# RH046_2.net
KiCad netlist of a schematic drawn in EAGLE
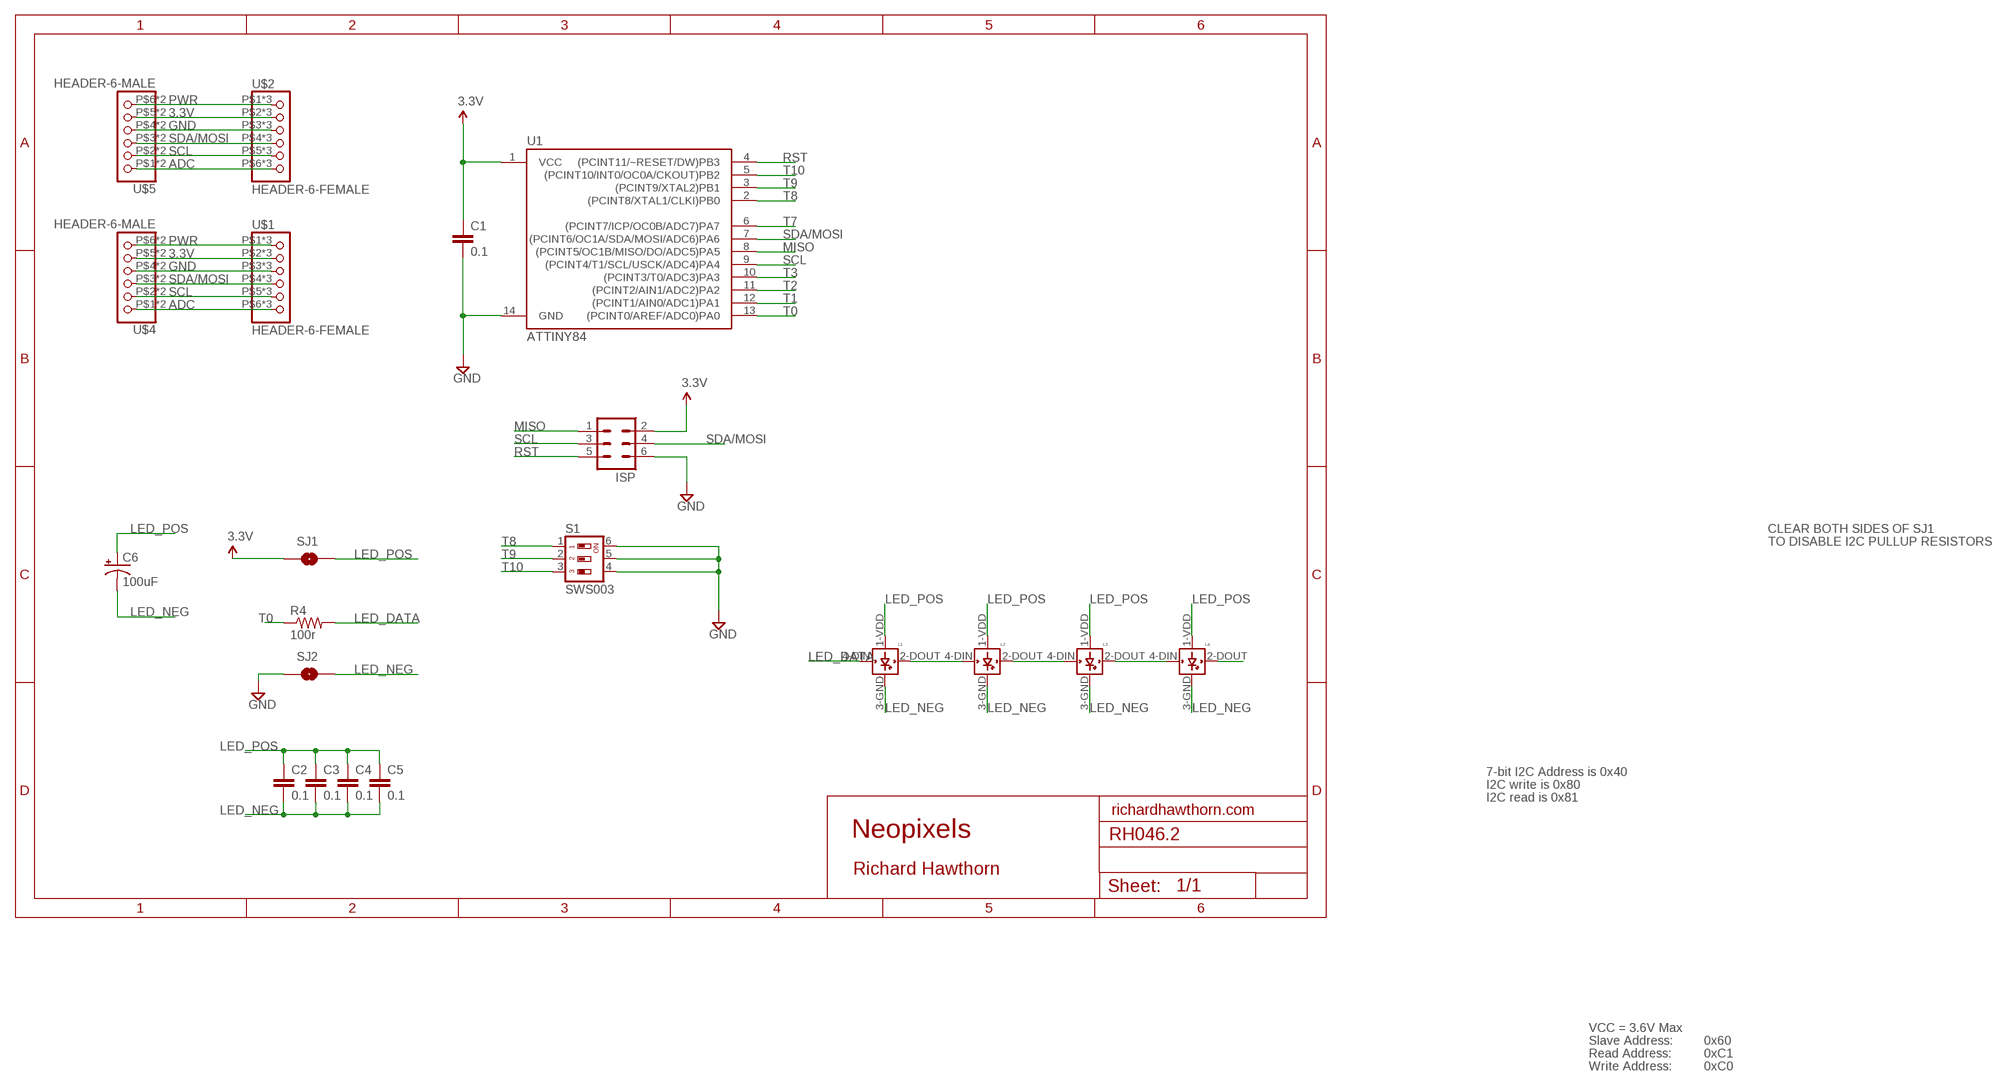
[diagram p0: schematic, sheet 1]

(export (version "E")
  (design (tool "Eeschema 10.0.6"))
  (components
    (comp (ref "C1")
      (value "0.1")
      (footprint "eagle-import:0603-CAP")
      (libsource (lib "eagle-import") (part "CAP0603-CAP"))
    )
    (comp (ref "C2")
      (value "0.1")
      (footprint "eagle-import:0603-CAP")
      (libsource (lib "eagle-import") (part "CAP0603-CAP"))
    )
    (comp (ref "C3")
      (value "0.1")
      (footprint "eagle-import:0603-CAP")
      (libsource (lib "eagle-import") (part "CAP0603-CAP"))
    )
    (comp (ref "C4")
      (value "0.1")
      (footprint "eagle-import:0603-CAP")
      (libsource (lib "eagle-import") (part "CAP0603-CAP"))
    )
    (comp (ref "C5")
      (value "0.1")
      (footprint "eagle-import:0603-CAP")
      (libsource (lib "eagle-import") (part "CAP0603-CAP"))
    )
    (comp (ref "C6")
      (value "100uF")
      (footprint "eagle-import:EIA7343")
      (libsource (lib "eagle-import") (part "100UF-10V-10%(TANT)"))
    )
    (comp (ref "ISP")
      (value "MA03-2")
      (footprint "eagle-import:MA03-2")
      (libsource (lib "eagle-import") (part "MA03-2"))
    )
    (comp (ref "L1")
      (value "WS2812B")
      (footprint "eagle-import:WS2812B")
      (libsource (lib "eagle-import") (part "WS2812B"))
    )
    (comp (ref "L2")
      (value "WS2812B")
      (footprint "eagle-import:WS2812B")
      (libsource (lib "eagle-import") (part "WS2812B"))
    )
    (comp (ref "L3")
      (value "WS2812B")
      (footprint "eagle-import:WS2812B")
      (libsource (lib "eagle-import") (part "WS2812B"))
    )
    (comp (ref "L4")
      (value "WS2812B")
      (footprint "eagle-import:WS2812B")
      (libsource (lib "eagle-import") (part "WS2812B"))
    )
    (comp (ref "R4")
      (value "100r")
      (footprint "eagle-import:0603-RES")
      (libsource (lib "eagle-import") (part "RESISTOR0603-RES"))
    )
    (comp (ref "S1")
      (value "SWS003")
      (footprint "eagle-import:SMS-003")
      (libsource (lib "eagle-import") (part "SWS003"))
    )
    (comp (ref "SJ1")
      (value "SOLDERJUMPERNO")
      (footprint "eagle-import:SJ_2S-NO")
      (libsource (lib "eagle-import") (part "SOLDERJUMPERNO"))
    )
    (comp (ref "SJ2")
      (value "SOLDERJUMPERNO")
      (footprint "eagle-import:SJ_2S-NO")
      (libsource (lib "eagle-import") (part "SOLDERJUMPERNO"))
    )
    (comp (ref "U$1")
      (value "HEADER-6-FEMALE")
      (footprint "eagle-import:2MMHEADER6")
      (libsource (lib "eagle-import") (part "HEADER-6-FEMALE"))
    )
    (comp (ref "U$2")
      (value "HEADER-6-FEMALE")
      (footprint "eagle-import:2MMHEADER6")
      (libsource (lib "eagle-import") (part "HEADER-6-FEMALE"))
    )
    (comp (ref "U$4")
      (value "HEADER-6-MALE")
      (footprint "eagle-import:2MMHEADERPIN6")
      (libsource (lib "eagle-import") (part "HEADER-6-MALE"))
    )
    (comp (ref "U$5")
      (value "HEADER-6-MALE")
      (footprint "eagle-import:2MMHEADERPIN6")
      (libsource (lib "eagle-import") (part "HEADER-6-MALE"))
    )
    (comp (ref "U1")
      (value "ATTINY84")
      (footprint "eagle-import:SO14")
      (libsource (lib "eagle-import") (part "ATTINY84"))
    )
  )
  (nets
    (net (code "1") (name "/ADC") (class "Default")
      (node (ref "U$1") (pin "P$14") (pinfunction "6_P$14") (pintype "passive"))
      (node (ref "U$1") (pin "P$22") (pinfunction "6_P$22") (pintype "passive"))
      (node (ref "U$1") (pin "P$6") (pinfunction "6_P$6") (pintype "passive"))
      (node (ref "U$2") (pin "P$14") (pinfunction "6_P$14") (pintype "passive"))
      (node (ref "U$2") (pin "P$22") (pinfunction "6_P$22") (pintype "passive"))
      (node (ref "U$2") (pin "P$6") (pinfunction "6_P$6") (pintype "passive"))
      (node (ref "U$4") (pin "P$1") (pinfunction "1_P$1") (pintype "passive"))
      (node (ref "U$4") (pin "P$9") (pinfunction "1_P$9") (pintype "passive"))
      (node (ref "U$5") (pin "P$1") (pinfunction "1_P$1") (pintype "passive"))
      (node (ref "U$5") (pin "P$9") (pinfunction "1_P$9") (pintype "passive"))
    )
    (net (code "2") (name "/LED_DATA") (class "Default")
      (node (ref "L1") (pin "4-DIN") (pinfunction "DIN_4-DIN") (pintype "input"))
      (node (ref "R4") (pin "2") (pinfunction "2_2") (pintype "passive"))
    )
    (net (code "3") (name "/LED_NEG") (class "Default")
      (node (ref "C2") (pin "2") (pinfunction "2_2") (pintype "passive"))
      (node (ref "C3") (pin "2") (pinfunction "2_2") (pintype "passive"))
      (node (ref "C4") (pin "2") (pinfunction "2_2") (pintype "passive"))
      (node (ref "C5") (pin "2") (pinfunction "2_2") (pintype "passive"))
      (node (ref "C6") (pin "C") (pinfunction "-_C") (pintype "passive"))
      (node (ref "L1") (pin "3-GND") (pinfunction "GND_3-GND") (pintype "bidirectional"))
      (node (ref "L2") (pin "3-GND") (pinfunction "GND_3-GND") (pintype "bidirectional"))
      (node (ref "L3") (pin "3-GND") (pinfunction "GND_3-GND") (pintype "bidirectional"))
      (node (ref "L4") (pin "3-GND") (pinfunction "GND_3-GND") (pintype "bidirectional"))
      (node (ref "SJ2") (pin "2") (pinfunction "2_2") (pintype "passive"))
    )
    (net (code "4") (name "/LED_POS") (class "Default")
      (node (ref "C2") (pin "1") (pinfunction "1_1") (pintype "passive"))
      (node (ref "C3") (pin "1") (pinfunction "1_1") (pintype "passive"))
      (node (ref "C4") (pin "1") (pinfunction "1_1") (pintype "passive"))
      (node (ref "C5") (pin "1") (pinfunction "1_1") (pintype "passive"))
      (node (ref "C6") (pin "A") (pinfunction "+_A") (pintype "passive"))
      (node (ref "L1") (pin "1-VDD") (pinfunction "VDD_1-VDD") (pintype "bidirectional"))
      (node (ref "L2") (pin "1-VDD") (pinfunction "VDD_1-VDD") (pintype "bidirectional"))
      (node (ref "L3") (pin "1-VDD") (pinfunction "VDD_1-VDD") (pintype "bidirectional"))
      (node (ref "L4") (pin "1-VDD") (pinfunction "VDD_1-VDD") (pintype "bidirectional"))
      (node (ref "SJ1") (pin "2") (pinfunction "2_2") (pintype "passive"))
    )
    (net (code "5") (name "/MISO") (class "Default")
      (node (ref "ISP") (pin "1") (pinfunction "1_1") (pintype "passive"))
      (node (ref "U1") (pin "8") (pinfunction "(PCINT5/OC1B/MISO/DO/ADC5)PA5_8") (pintype "bidirectional"))
    )
    (net (code "6") (name "/PWR") (class "Default")
      (node (ref "U$1") (pin "P$1") (pinfunction "1_P$1") (pintype "passive"))
      (node (ref "U$1") (pin "P$17") (pinfunction "1_P$17") (pintype "passive"))
      (node (ref "U$1") (pin "P$9") (pinfunction "1_P$9") (pintype "passive"))
      (node (ref "U$2") (pin "P$1") (pinfunction "1_P$1") (pintype "passive"))
      (node (ref "U$2") (pin "P$17") (pinfunction "1_P$17") (pintype "passive"))
      (node (ref "U$2") (pin "P$9") (pinfunction "1_P$9") (pintype "passive"))
      (node (ref "U$4") (pin "P$14") (pinfunction "6_P$14") (pintype "passive"))
      (node (ref "U$4") (pin "P$6") (pinfunction "6_P$6") (pintype "passive"))
      (node (ref "U$5") (pin "P$14") (pinfunction "6_P$14") (pintype "passive"))
      (node (ref "U$5") (pin "P$6") (pinfunction "6_P$6") (pintype "passive"))
    )
    (net (code "7") (name "/RST") (class "Default")
      (node (ref "ISP") (pin "5") (pinfunction "5_5") (pintype "passive"))
      (node (ref "U1") (pin "4") (pinfunction "(PCINT11/~{RESET/DW})PB3_4") (pintype "bidirectional"))
    )
    (net (code "8") (name "/SCL") (class "Default")
      (node (ref "ISP") (pin "3") (pinfunction "3_3") (pintype "passive"))
      (node (ref "U$1") (pin "P$13") (pinfunction "5_P$13") (pintype "passive"))
      (node (ref "U$1") (pin "P$21") (pinfunction "5_P$21") (pintype "passive"))
      (node (ref "U$1") (pin "P$5") (pinfunction "5_P$5") (pintype "passive"))
      (node (ref "U$2") (pin "P$13") (pinfunction "5_P$13") (pintype "passive"))
      (node (ref "U$2") (pin "P$21") (pinfunction "5_P$21") (pintype "passive"))
      (node (ref "U$2") (pin "P$5") (pinfunction "5_P$5") (pintype "passive"))
      (node (ref "U$4") (pin "P$10") (pinfunction "2_P$10") (pintype "passive"))
      (node (ref "U$4") (pin "P$2") (pinfunction "2_P$2") (pintype "passive"))
      (node (ref "U$5") (pin "P$10") (pinfunction "2_P$10") (pintype "passive"))
      (node (ref "U$5") (pin "P$2") (pinfunction "2_P$2") (pintype "passive"))
      (node (ref "U1") (pin "9") (pinfunction "(PCINT4/T1/SCL/USCK/ADC4)PA4_9") (pintype "bidirectional"))
    )
    (net (code "9") (name "/SDA{slash}MOSI") (class "Default")
      (node (ref "ISP") (pin "4") (pinfunction "4_4") (pintype "passive"))
      (node (ref "U$1") (pin "P$12") (pinfunction "4_P$12") (pintype "passive"))
      (node (ref "U$1") (pin "P$20") (pinfunction "4_P$20") (pintype "passive"))
      (node (ref "U$1") (pin "P$4") (pinfunction "4_P$4") (pintype "passive"))
      (node (ref "U$2") (pin "P$12") (pinfunction "4_P$12") (pintype "passive"))
      (node (ref "U$2") (pin "P$20") (pinfunction "4_P$20") (pintype "passive"))
      (node (ref "U$2") (pin "P$4") (pinfunction "4_P$4") (pintype "passive"))
      (node (ref "U$4") (pin "P$11") (pinfunction "3_P$11") (pintype "passive"))
      (node (ref "U$4") (pin "P$3") (pinfunction "3_P$3") (pintype "passive"))
      (node (ref "U$5") (pin "P$11") (pinfunction "3_P$11") (pintype "passive"))
      (node (ref "U$5") (pin "P$3") (pinfunction "3_P$3") (pintype "passive"))
      (node (ref "U1") (pin "7") (pinfunction "(PCINT6/OC1A/SDA/MOSI/ADC6)PA6_7") (pintype "bidirectional"))
    )
    (net (code "10") (name "/T0") (class "Default")
      (node (ref "R4") (pin "1") (pinfunction "1_1") (pintype "passive"))
      (node (ref "U1") (pin "13") (pinfunction "(PCINT0/AREF/ADC0)PA0_13") (pintype "bidirectional"))
    )
    (net (code "11") (name "/T1") (class "Default")
      (node (ref "U1") (pin "12") (pinfunction "(PCINT1/AIN0/ADC1)PA1_12") (pintype "bidirectional"))
    )
    (net (code "12") (name "/T2") (class "Default")
      (node (ref "U1") (pin "11") (pinfunction "(PCINT2/AIN1/ADC2)PA2_11") (pintype "bidirectional"))
    )
    (net (code "13") (name "/T3") (class "Default")
      (node (ref "U1") (pin "10") (pinfunction "(PCINT3/T0/ADC3)PA3_10") (pintype "bidirectional"))
    )
    (net (code "14") (name "/T7") (class "Default")
      (node (ref "U1") (pin "6") (pinfunction "(PCINT7/ICP/OC0B/ADC7)PA7_6") (pintype "bidirectional"))
    )
    (net (code "15") (name "/T8") (class "Default")
      (node (ref "S1") (pin "1") (pinfunction "1_1") (pintype "passive"))
      (node (ref "U1") (pin "2") (pinfunction "(PCINT8/XTAL1/CLKI)PB0_2") (pintype "bidirectional"))
    )
    (net (code "16") (name "/T9") (class "Default")
      (node (ref "S1") (pin "2") (pinfunction "2_2") (pintype "passive"))
      (node (ref "U1") (pin "3") (pinfunction "(PCINT9/XTAL2)PB1_3") (pintype "bidirectional"))
    )
    (net (code "17") (name "/T10") (class "Default")
      (node (ref "S1") (pin "3") (pinfunction "3_3") (pintype "passive"))
      (node (ref "U1") (pin "5") (pinfunction "(PCINT10/INT0/OC0A/CKOUT)PB2_5") (pintype "bidirectional"))
    )
    (net (code "18") (name "3.3V") (class "Default")
      (node (ref "C1") (pin "1") (pinfunction "1_1") (pintype "passive"))
      (node (ref "ISP") (pin "2") (pinfunction "2_2") (pintype "passive"))
      (node (ref "SJ1") (pin "1") (pinfunction "1_1") (pintype "passive"))
      (node (ref "U$1") (pin "P$10") (pinfunction "2_P$10") (pintype "passive"))
      (node (ref "U$1") (pin "P$18") (pinfunction "2_P$18") (pintype "passive"))
      (node (ref "U$1") (pin "P$2") (pinfunction "2_P$2") (pintype "passive"))
      (node (ref "U$2") (pin "P$10") (pinfunction "2_P$10") (pintype "passive"))
      (node (ref "U$2") (pin "P$18") (pinfunction "2_P$18") (pintype "passive"))
      (node (ref "U$2") (pin "P$2") (pinfunction "2_P$2") (pintype "passive"))
      (node (ref "U$4") (pin "P$13") (pinfunction "5_P$13") (pintype "passive"))
      (node (ref "U$4") (pin "P$5") (pinfunction "5_P$5") (pintype "passive"))
      (node (ref "U$5") (pin "P$13") (pinfunction "5_P$13") (pintype "passive"))
      (node (ref "U$5") (pin "P$5") (pinfunction "5_P$5") (pintype "passive"))
      (node (ref "U1") (pin "1") (pinfunction "VCC_1") (pintype "bidirectional"))
    )
    (net (code "19") (name "GND") (class "Default")
      (node (ref "C1") (pin "2") (pinfunction "2_2") (pintype "passive"))
      (node (ref "ISP") (pin "6") (pinfunction "6_6") (pintype "passive"))
      (node (ref "S1") (pin "4") (pinfunction "4_4") (pintype "passive"))
      (node (ref "S1") (pin "5") (pinfunction "5_5") (pintype "passive"))
      (node (ref "S1") (pin "6") (pinfunction "6_6") (pintype "passive"))
      (node (ref "SJ2") (pin "1") (pinfunction "1_1") (pintype "passive"))
      (node (ref "U$1") (pin "P$11") (pinfunction "3_P$11") (pintype "passive"))
      (node (ref "U$1") (pin "P$19") (pinfunction "3_P$19") (pintype "passive"))
      (node (ref "U$1") (pin "P$3") (pinfunction "3_P$3") (pintype "passive"))
      (node (ref "U$2") (pin "P$11") (pinfunction "3_P$11") (pintype "passive"))
      (node (ref "U$2") (pin "P$19") (pinfunction "3_P$19") (pintype "passive"))
      (node (ref "U$2") (pin "P$3") (pinfunction "3_P$3") (pintype "passive"))
      (node (ref "U$4") (pin "P$12") (pinfunction "4_P$12") (pintype "passive"))
      (node (ref "U$4") (pin "P$4") (pinfunction "4_P$4") (pintype "passive"))
      (node (ref "U$5") (pin "P$12") (pinfunction "4_P$12") (pintype "passive"))
      (node (ref "U$5") (pin "P$4") (pinfunction "4_P$4") (pintype "passive"))
      (node (ref "U1") (pin "14") (pinfunction "GND_14") (pintype "bidirectional"))
    )
    (net (code "20") (name "Net-(L1-DOUT)") (class "Default")
      (node (ref "L1") (pin "2-DOUT") (pinfunction "DOUT_2-DOUT") (pintype "output"))
      (node (ref "L2") (pin "4-DIN") (pinfunction "DIN_4-DIN") (pintype "input"))
    )
    (net (code "21") (name "Net-(L2-DOUT)") (class "Default")
      (node (ref "L2") (pin "2-DOUT") (pinfunction "DOUT_2-DOUT") (pintype "output"))
      (node (ref "L3") (pin "4-DIN") (pinfunction "DIN_4-DIN") (pintype "input"))
    )
    (net (code "22") (name "Net-(L3-DOUT)") (class "Default")
      (node (ref "L3") (pin "2-DOUT") (pinfunction "DOUT_2-DOUT") (pintype "output"))
      (node (ref "L4") (pin "4-DIN") (pinfunction "DIN_4-DIN") (pintype "input"))
    )
    (net (code "23") (name "unconnected-(L4-DOUT-Pad2-DOUT)") (class "Default")
      (node (ref "L4") (pin "2-DOUT") (pinfunction "DOUT_2-DOUT") (pintype "output"))
    )
  )
)
